# ds3231.net
KiCad netlist of a schematic drawn in EAGLE
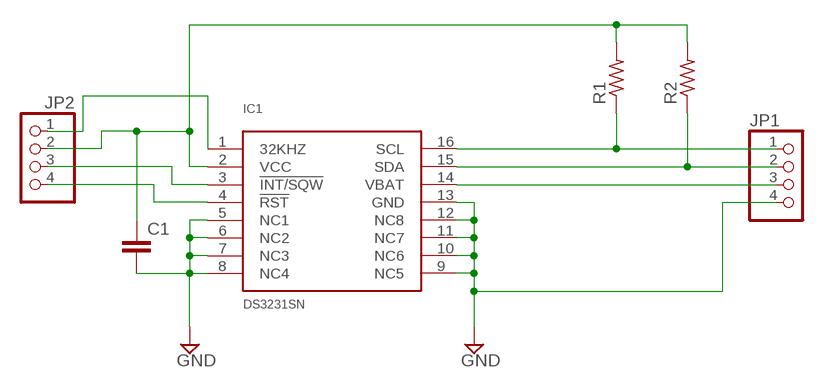
[diagram p0: schematic, sheet 1]

(export (version "E")
  (design (tool "Eeschema 10.0.6"))
  (components
    (comp (ref "C1")
      (value "C5/3.5")
      (footprint "eagle-import:C5B3.5")
      (libsource (lib "eagle-import") (part "C5/3.5"))
    )
    (comp (ref "IC1")
      (value "DS3231SN")
      (footprint "eagle-import:SO16W")
      (libsource (lib "eagle-import") (part "DS3231SN"))
    )
    (comp (ref "JP1")
      (value "PINHD-1X4")
      (footprint "eagle-import:1X04")
      (libsource (lib "eagle-import") (part "PINHD-1X4"))
    )
    (comp (ref "JP2")
      (value "PINHD-1X4")
      (footprint "eagle-import:1X04")
      (libsource (lib "eagle-import") (part "PINHD-1X4"))
    )
    (comp (ref "R1")
      (value "R-US_0207/10")
      (footprint "eagle-import:0207_10")
      (libsource (lib "eagle-import") (part "R-US_0207/10"))
    )
    (comp (ref "R2")
      (value "R-US_0207/10")
      (footprint "eagle-import:0207_10")
      (libsource (lib "eagle-import") (part "R-US_0207/10"))
    )
  )
  (nets
    (net (code "1") (name "GND") (class "Default")
      (node (ref "C1") (pin "2") (pinfunction "2_2") (pintype "passive"))
      (node (ref "IC1") (pin "10") (pinfunction "NC6_10") (pintype "bidirectional"))
      (node (ref "IC1") (pin "11") (pinfunction "NC7_11") (pintype "bidirectional"))
      (node (ref "IC1") (pin "12") (pinfunction "NC8_12") (pintype "bidirectional"))
      (node (ref "IC1") (pin "13") (pinfunction "GND_13") (pintype "bidirectional"))
      (node (ref "IC1") (pin "5") (pinfunction "NC1_5") (pintype "bidirectional"))
      (node (ref "IC1") (pin "6") (pinfunction "NC2_6") (pintype "bidirectional"))
      (node (ref "IC1") (pin "7") (pinfunction "NC3_7") (pintype "bidirectional"))
      (node (ref "IC1") (pin "8") (pinfunction "NC4_8") (pintype "bidirectional"))
      (node (ref "IC1") (pin "9") (pinfunction "NC5_9") (pintype "bidirectional"))
      (node (ref "JP1") (pin "4") (pinfunction "4_4") (pintype "passive"))
    )
    (net (code "2") (name "Net-(IC1-32KHZ)") (class "Default")
      (node (ref "IC1") (pin "1") (pinfunction "32KHZ_1") (pintype "bidirectional"))
      (node (ref "JP2") (pin "1") (pinfunction "1_1") (pintype "passive"))
    )
    (net (code "3") (name "Net-(IC1-SCL)") (class "Default")
      (node (ref "IC1") (pin "16") (pinfunction "SCL_16") (pintype "bidirectional"))
      (node (ref "JP1") (pin "1") (pinfunction "1_1") (pintype "passive"))
      (node (ref "R1") (pin "1") (pinfunction "1_1") (pintype "passive"))
    )
    (net (code "4") (name "Net-(IC1-SDA)") (class "Default")
      (node (ref "IC1") (pin "15") (pinfunction "SDA_15") (pintype "bidirectional"))
      (node (ref "JP1") (pin "2") (pinfunction "2_2") (pintype "passive"))
      (node (ref "R2") (pin "1") (pinfunction "1_1") (pintype "passive"))
    )
    (net (code "5") (name "Net-(IC1-VBAT)") (class "Default")
      (node (ref "IC1") (pin "14") (pinfunction "VBAT_14") (pintype "bidirectional"))
      (node (ref "JP1") (pin "3") (pinfunction "3_3") (pintype "passive"))
    )
    (net (code "6") (name "Net-(IC1-VCC)") (class "Default")
      (node (ref "C1") (pin "1") (pinfunction "1_1") (pintype "passive"))
      (node (ref "IC1") (pin "2") (pinfunction "VCC_2") (pintype "bidirectional"))
      (node (ref "JP2") (pin "2") (pinfunction "2_2") (pintype "passive"))
      (node (ref "R1") (pin "2") (pinfunction "2_2") (pintype "passive"))
      (node (ref "R2") (pin "2") (pinfunction "2_2") (pintype "passive"))
    )
    (net (code "7") (name "Net-(IC1-~{INT{slash}SQW})") (class "Default")
      (node (ref "IC1") (pin "3") (pinfunction "~{INT/SQW}_3") (pintype "bidirectional"))
      (node (ref "JP2") (pin "3") (pinfunction "3_3") (pintype "passive"))
    )
    (net (code "8") (name "Net-(IC1-~{RST})") (class "Default")
      (node (ref "IC1") (pin "4") (pinfunction "~{RST}_4") (pintype "bidirectional"))
      (node (ref "JP2") (pin "4") (pinfunction "4_4") (pintype "passive"))
    )
  )
)
